# uLED_v1.net
KiCad netlist of a schematic drawn in EAGLE
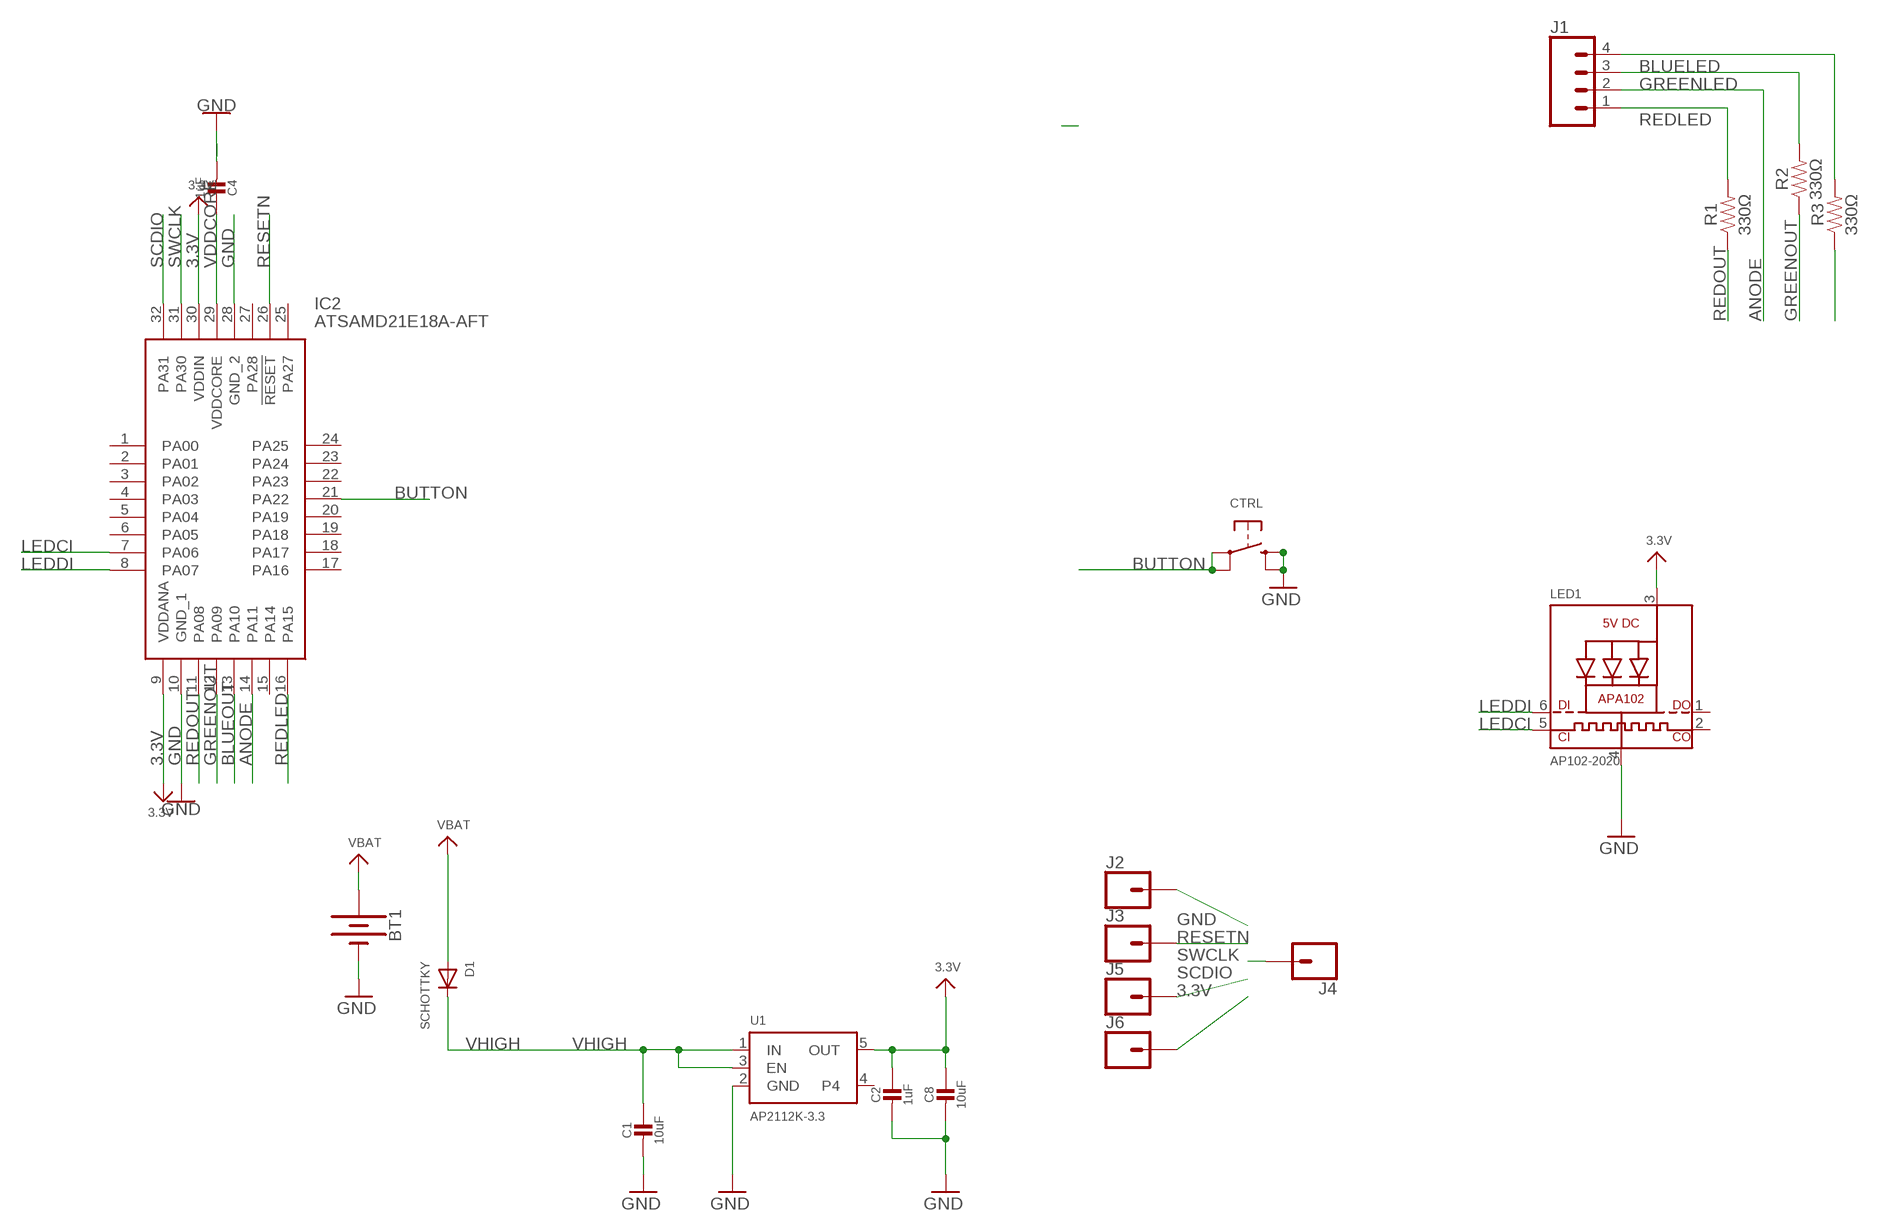
[diagram p0: schematic, sheet 1]

(export (version "E")
  (design (tool "Eeschema 10.0.6"))
  (components
    (comp (ref "BT1")
      (value "BATTERY-12MM_SMD")
      (footprint "eagle-import:BATTCON_12MM")
      (libsource (lib "eagle-import") (part "BATTERY-12MM_SMD"))
    )
    (comp (ref "C1")
      (value "10uF")
      (footprint "eagle-import:0805-NO")
      (libsource (lib "eagle-import") (part "CAP_CERAMIC0805-NOOUTLINE"))
    )
    (comp (ref "C2")
      (value "1uF")
      (footprint "eagle-import:0603-NO")
      (libsource (lib "eagle-import") (part "CAP_CERAMIC0603_NO"))
    )
    (comp (ref "C4")
      (value "1uF")
      (footprint "eagle-import:0603-NO")
      (libsource (lib "eagle-import") (part "CAP_CERAMIC0603_NO"))
    )
    (comp (ref "C8")
      (value "10uF")
      (footprint "eagle-import:0805-NO")
      (libsource (lib "eagle-import") (part "CAP_CERAMIC0805-NOOUTLINE"))
    )
    (comp (ref "CTRL")
      (value "SWITCH_TACT_SMT4.6X2.8")
      (footprint "eagle-import:BTN_KMR2_4.6X2.8")
      (libsource (lib "eagle-import") (part "SWITCH_TACT_SMT4.6X2.8"))
    )
    (comp (ref "D1")
      (value "SCHOTTKY")
      (footprint "eagle-import:SOD-123FL")
      (libsource (lib "eagle-import") (part "DIODE_SOD-123FL"))
    )
    (comp (ref "IC2")
      (value "ATSAMD21E18A-AFT")
      (footprint "eagle-import:QFP80P900X900X120-32N")
      (fields (field (name "MOUSER_PART_NUMBER") "556-ATSAMD21E18A-AFT"))
      (libsource (lib "eagle-import") (part "ATSAMD21E18A-AFT"))
    )
    (comp (ref "J1")
      (value "CONN_04")
      (footprint "eagle-import:1X04")
      (libsource (lib "eagle-import") (part "CONN_04"))
    )
    (comp (ref "J2")
      (value "CONN_01")
      (footprint "eagle-import:1X01")
      (libsource (lib "eagle-import") (part "CONN_01"))
    )
    (comp (ref "J3")
      (value "CONN_01")
      (footprint "eagle-import:1X01")
      (libsource (lib "eagle-import") (part "CONN_01"))
    )
    (comp (ref "J4")
      (value "CONN_01")
      (footprint "eagle-import:1X01")
      (libsource (lib "eagle-import") (part "CONN_01"))
    )
    (comp (ref "J5")
      (value "CONN_01")
      (footprint "eagle-import:1X01")
      (libsource (lib "eagle-import") (part "CONN_01"))
    )
    (comp (ref "J6")
      (value "CONN_01")
      (footprint "eagle-import:1X01")
      (libsource (lib "eagle-import") (part "CONN_01"))
    )
    (comp (ref "LED1")
      (value "AP102-2020")
      (footprint "eagle-import:APA102_2020")
      (libsource (lib "eagle-import") (part "APA1022020"))
    )
    (comp (ref "R1")
      (value "330Ω")
      (footprint "eagle-import:0603")
      (libsource (lib "eagle-import") (part "0.27OHM-0603-1/10W-1%"))
    )
    (comp (ref "R2")
      (value "330Ω")
      (footprint "eagle-import:0603")
      (libsource (lib "eagle-import") (part "0.27OHM-0603-1/10W-1%"))
    )
    (comp (ref "R3")
      (value "330Ω")
      (footprint "eagle-import:0603")
      (libsource (lib "eagle-import") (part "0.27OHM-0603-1/10W-1%"))
    )
    (comp (ref "U1")
      (value "AP2112K-3.3")
      (footprint "eagle-import:SOT23-5")
      (libsource (lib "eagle-import") (part "VREG_SOT23-5"))
    )
  )
  (nets
    (net (code "1") (name "/ANODE") (class "Default")
      (node (ref "IC2") (pin "14") (pinfunction "PA11_14") (pintype "bidirectional"))
      (node (ref "J1") (pin "2") (pinfunction "2_2") (pintype "passive"))
    )
    (net (code "2") (name "/BLUELED") (class "Default")
      (node (ref "J1") (pin "4") (pinfunction "4_4") (pintype "passive"))
      (node (ref "R3") (pin "2") (pinfunction "2_2") (pintype "passive"))
    )
    (net (code "3") (name "/BLUEOUT") (class "Default")
      (node (ref "IC2") (pin "13") (pinfunction "PA10_13") (pintype "bidirectional"))
      (node (ref "R3") (pin "1") (pinfunction "1_1") (pintype "passive"))
    )
    (net (code "4") (name "/BUTTON") (class "Default")
      (node (ref "CTRL") (pin "A") (pinfunction "P_A") (pintype "passive"))
      (node (ref "CTRL") (pin "A'") (pinfunction "P1_A'") (pintype "passive"))
      (node (ref "IC2") (pin "21") (pinfunction "PA22_21") (pintype "bidirectional"))
    )
    (net (code "5") (name "/GREENLED") (class "Default")
      (node (ref "J1") (pin "3") (pinfunction "3_3") (pintype "passive"))
      (node (ref "R2") (pin "2") (pinfunction "2_2") (pintype "passive"))
    )
    (net (code "6") (name "/GREENOUT") (class "Default")
      (node (ref "IC2") (pin "12") (pinfunction "PA09_12") (pintype "bidirectional"))
      (node (ref "R2") (pin "1") (pinfunction "1_1") (pintype "passive"))
    )
    (net (code "7") (name "/LEDCI") (class "Default")
      (node (ref "IC2") (pin "7") (pinfunction "PA06_7") (pintype "bidirectional"))
      (node (ref "LED1") (pin "5") (pinfunction "CKI_5") (pintype "input"))
    )
    (net (code "8") (name "/LEDDI") (class "Default")
      (node (ref "IC2") (pin "8") (pinfunction "PA07_8") (pintype "bidirectional"))
      (node (ref "LED1") (pin "6") (pinfunction "DI_6") (pintype "input"))
    )
    (net (code "9") (name "/REDLED") (class "Default")
      (node (ref "IC2") (pin "16") (pinfunction "PA15_16") (pintype "bidirectional"))
      (node (ref "J1") (pin "1") (pinfunction "1_1") (pintype "passive"))
      (node (ref "R1") (pin "2") (pinfunction "2_2") (pintype "passive"))
    )
    (net (code "10") (name "/REDOUT") (class "Default")
      (node (ref "IC2") (pin "11") (pinfunction "PA08_11") (pintype "bidirectional"))
      (node (ref "R1") (pin "1") (pinfunction "1_1") (pintype "passive"))
    )
    (net (code "11") (name "/RESETN") (class "Default")
      (node (ref "IC2") (pin "26") (pinfunction "~{RESET}_26") (pintype "bidirectional"))
      (node (ref "J3") (pin "1") (pinfunction "1_1") (pintype "passive"))
    )
    (net (code "12") (name "/SCDIO") (class "Default")
      (node (ref "IC2") (pin "32") (pinfunction "PA31_32") (pintype "bidirectional"))
      (node (ref "J5") (pin "1") (pinfunction "1_1") (pintype "passive"))
    )
    (net (code "13") (name "/SWCLK") (class "Default")
      (node (ref "IC2") (pin "31") (pinfunction "PA30_31") (pintype "bidirectional"))
      (node (ref "J4") (pin "1") (pinfunction "1_1") (pintype "passive"))
    )
    (net (code "14") (name "/VDDCORE") (class "Default")
      (node (ref "C4") (pin "1") (pinfunction "1_1") (pintype "passive"))
      (node (ref "IC2") (pin "29") (pinfunction "VDDCORE_29") (pintype "bidirectional"))
    )
    (net (code "15") (name "/VHIGH") (class "Default")
      (node (ref "C1") (pin "1") (pinfunction "1_1") (pintype "passive"))
      (node (ref "D1") (pin "C") (pinfunction "C_C") (pintype "passive"))
      (node (ref "U1") (pin "1") (pinfunction "IN_1") (pintype "power_in"))
      (node (ref "U1") (pin "3") (pinfunction "EN_3") (pintype "input"))
    )
    (net (code "16") (name "3.3V") (class "Default")
      (node (ref "C2") (pin "1") (pinfunction "1_1") (pintype "passive"))
      (node (ref "C8") (pin "1") (pinfunction "1_1") (pintype "passive"))
      (node (ref "IC2") (pin "30") (pinfunction "VDDIN_30") (pintype "bidirectional"))
      (node (ref "IC2") (pin "9") (pinfunction "VDDANA_9") (pintype "bidirectional"))
      (node (ref "J6") (pin "1") (pinfunction "1_1") (pintype "passive"))
      (node (ref "LED1") (pin "3") (pinfunction "VDD_3") (pintype "power_in"))
      (node (ref "U1") (pin "5") (pinfunction "OUT_5") (pintype "power_in"))
    )
    (net (code "17") (name "GND") (class "Default")
      (node (ref "BT1") (pin "GND") (pinfunction "-_GND") (pintype "power_in"))
      (node (ref "C1") (pin "2") (pinfunction "2_2") (pintype "passive"))
      (node (ref "C2") (pin "2") (pinfunction "2_2") (pintype "passive"))
      (node (ref "C4") (pin "2") (pinfunction "2_2") (pintype "passive"))
      (node (ref "C8") (pin "2") (pinfunction "2_2") (pintype "passive"))
      (node (ref "CTRL") (pin "B") (pinfunction "S_B") (pintype "passive"))
      (node (ref "CTRL") (pin "B'") (pinfunction "S1_B'") (pintype "passive"))
      (node (ref "IC2") (pin "10") (pinfunction "GND_1_10") (pintype "bidirectional"))
      (node (ref "IC2") (pin "28") (pinfunction "GND_2_28") (pintype "bidirectional"))
      (node (ref "J2") (pin "1") (pinfunction "1_1") (pintype "passive"))
      (node (ref "LED1") (pin "4") (pinfunction "GND_4") (pintype "power_in"))
      (node (ref "U1") (pin "2") (pinfunction "GND_2") (pintype "power_in"))
    )
    (net (code "18") (name "VBAT") (class "Default")
      (node (ref "BT1") (pin "PWR@1") (pinfunction "+_PWR@1") (pintype "power_in"))
      (node (ref "D1") (pin "A") (pinfunction "A_A") (pintype "passive"))
    )
    (net (code "19") (name "unconnected-(IC2-PA00-Pad1)") (class "Default")
      (node (ref "IC2") (pin "1") (pinfunction "PA00_1") (pintype "bidirectional"))
    )
    (net (code "20") (name "unconnected-(IC2-PA01-Pad2)") (class "Default")
      (node (ref "IC2") (pin "2") (pinfunction "PA01_2") (pintype "bidirectional"))
    )
    (net (code "21") (name "unconnected-(IC2-PA02-Pad3)") (class "Default")
      (node (ref "IC2") (pin "3") (pinfunction "PA02_3") (pintype "bidirectional"))
    )
    (net (code "22") (name "unconnected-(IC2-PA03-Pad4)") (class "Default")
      (node (ref "IC2") (pin "4") (pinfunction "PA03_4") (pintype "bidirectional"))
    )
    (net (code "23") (name "unconnected-(IC2-PA04-Pad5)") (class "Default")
      (node (ref "IC2") (pin "5") (pinfunction "PA04_5") (pintype "bidirectional"))
    )
    (net (code "24") (name "unconnected-(IC2-PA05-Pad6)") (class "Default")
      (node (ref "IC2") (pin "6") (pinfunction "PA05_6") (pintype "bidirectional"))
    )
    (net (code "25") (name "unconnected-(IC2-PA14-Pad15)") (class "Default")
      (node (ref "IC2") (pin "15") (pinfunction "PA14_15") (pintype "bidirectional"))
    )
    (net (code "26") (name "unconnected-(IC2-PA16-Pad17)") (class "Default")
      (node (ref "IC2") (pin "17") (pinfunction "PA16_17") (pintype "bidirectional"))
    )
    (net (code "27") (name "unconnected-(IC2-PA17-Pad18)") (class "Default")
      (node (ref "IC2") (pin "18") (pinfunction "PA17_18") (pintype "bidirectional"))
    )
    (net (code "28") (name "unconnected-(IC2-PA18-Pad19)") (class "Default")
      (node (ref "IC2") (pin "19") (pinfunction "PA18_19") (pintype "bidirectional"))
    )
    (net (code "29") (name "unconnected-(IC2-PA19-Pad20)") (class "Default")
      (node (ref "IC2") (pin "20") (pinfunction "PA19_20") (pintype "bidirectional"))
    )
    (net (code "30") (name "unconnected-(IC2-PA23-Pad22)") (class "Default")
      (node (ref "IC2") (pin "22") (pinfunction "PA23_22") (pintype "bidirectional"))
    )
    (net (code "31") (name "unconnected-(IC2-PA24-Pad23)") (class "Default")
      (node (ref "IC2") (pin "23") (pinfunction "PA24_23") (pintype "bidirectional"))
    )
    (net (code "32") (name "unconnected-(IC2-PA25-Pad24)") (class "Default")
      (node (ref "IC2") (pin "24") (pinfunction "PA25_24") (pintype "bidirectional"))
    )
    (net (code "33") (name "unconnected-(IC2-PA27-Pad25)") (class "Default")
      (node (ref "IC2") (pin "25") (pinfunction "PA27_25") (pintype "bidirectional"))
    )
    (net (code "34") (name "unconnected-(IC2-PA28-Pad27)") (class "Default")
      (node (ref "IC2") (pin "27") (pinfunction "PA28_27") (pintype "bidirectional"))
    )
    (net (code "35") (name "unconnected-(LED1-CKO-Pad2)") (class "Default")
      (node (ref "LED1") (pin "2") (pinfunction "CKO_2") (pintype "output"))
    )
    (net (code "36") (name "unconnected-(LED1-DO-Pad1)") (class "Default")
      (node (ref "LED1") (pin "1") (pinfunction "DO_1") (pintype "output"))
    )
    (net (code "37") (name "unconnected-(U1-P4-Pad4)") (class "Default")
      (node (ref "U1") (pin "4") (pinfunction "P4_4") (pintype "bidirectional"))
    )
  )
)
